# SoC.net
KiCad netlist of a schematic drawn in Altium Designer
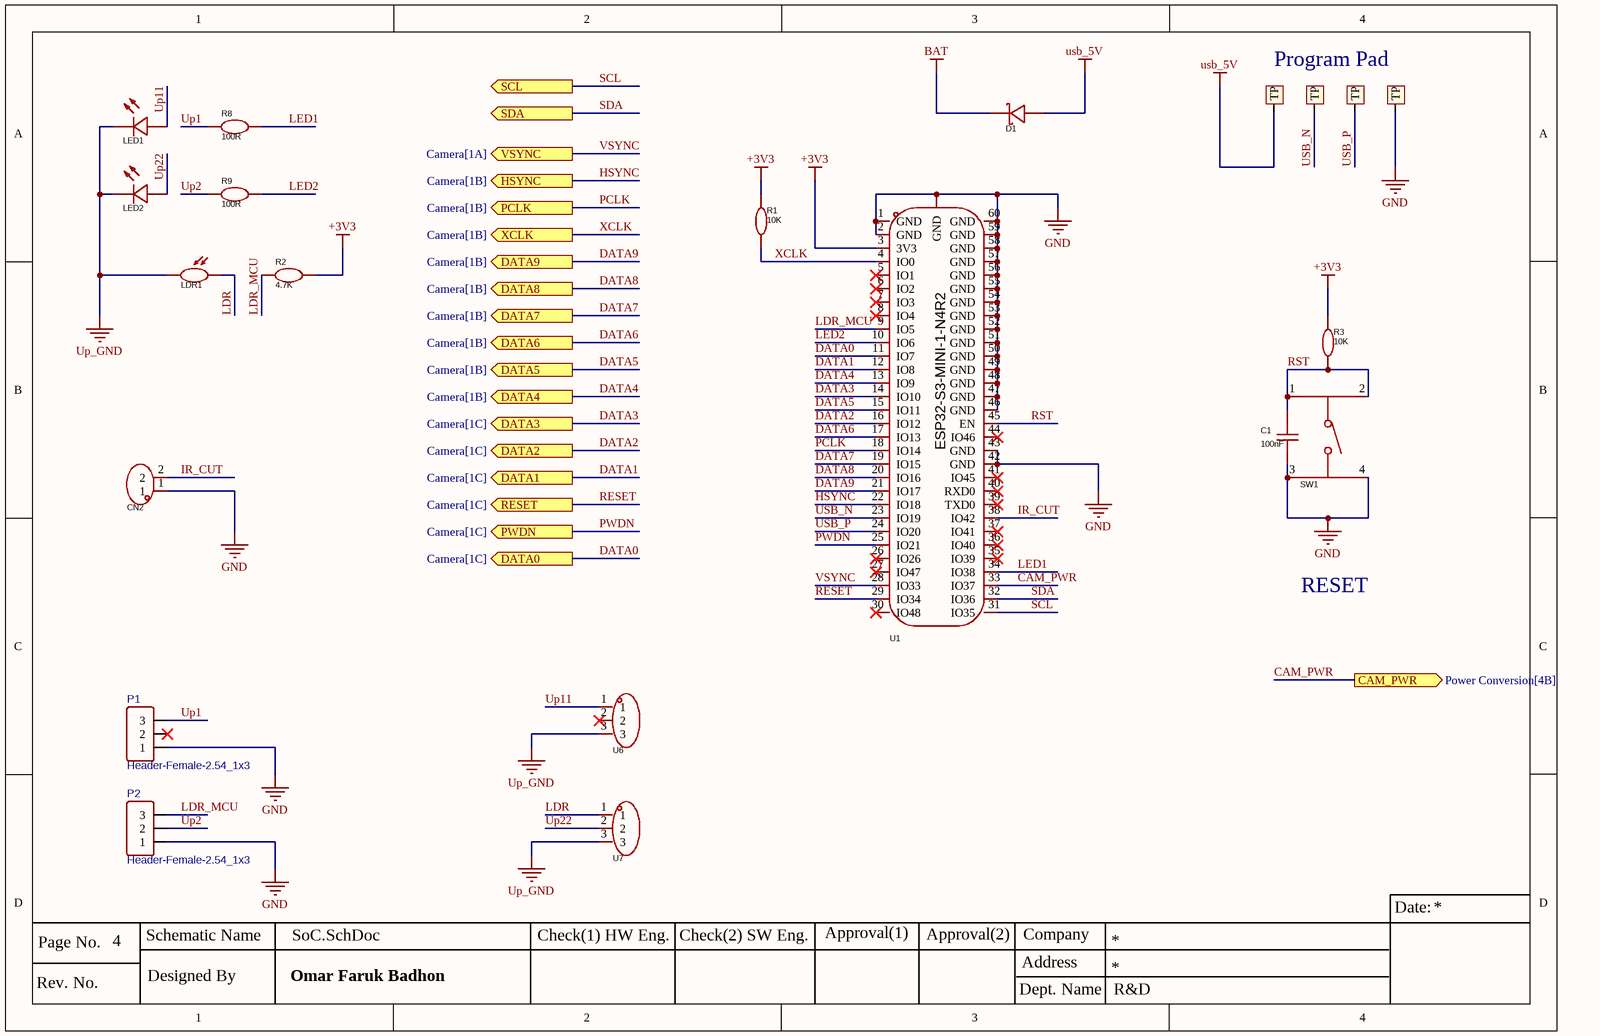
[diagram p0: SoC.SchDoc]

(export (version "E")
  (design (tool "Eeschema 10.0.6"))
  (components
    (comp (ref "C1")
      (value "100nF")
      (footprint "100nF SMD Ceramic 201")
      (description "10V 100nF X5R ±10% 0201 Multilayer Ceramic Capacitors MLCC - SMD/SMT ROHS")
      (fields
        (field (name "MANUFACTURER") "muRata(村田)")
        (field (name "MANUFACTURER PART") "GRM033R61A104KE84D")
      )
      (libsource (lib "Esp32 CAM SCH") (part "100nF SMD Ceramic 201"))
    )
    (comp (ref "CN2")
      (value "HDGC1501WV-2P")
      (footprint "2P white Connector 1.5mm")
      (fields (field (name "MANUFACTURER") "HDGC(华德共创)"))
      (libsource (lib "Esp32 CAM SCH") (part "2P Connector 1.5mm"))
    )
    (comp (ref "D1")
      (value "MBR120VLSFT1G")
      (footprint "Schottky Diode")
      (description "20V 300mV@1A 1A SOD-123FL Schottky Diodes ROHS")
      (fields (field (name "MANUFACTURER") "onsemi(安森美)"))
      (libsource (lib "Esp32 CAM SCH") (part "Schottky Diode"))
    )
    (comp (ref "LDR1")
      (value "GT36528")
      (footprint "LDR")
      (description "SMD,2.4x3.6mm Photoresistors ROHS")
      (fields (field (name "MANUFACTURER") "JCHL(晶创和立)"))
      (libsource (lib "Esp32 CAM SCH") (part "LDR"))
    )
    (comp (ref "LED1")
      (value "XYC-IRC18C-24")
      (footprint "LED SMD")
      (fields (field (name "MANUFACTURER") "NEWOPTO(鑫永诚光电)"))
      (libsource (lib "Esp32 CAM SCH") (part "LED SMD"))
    )
    (comp (ref "LED2")
      (value "XYC-IRC18C-24")
      (footprint "LED SMD")
      (fields (field (name "MANUFACTURER") "NEWOPTO(鑫永诚光电)"))
      (libsource (lib "Esp32 CAM SCH") (part "LED SMD"))
    )
    (comp (ref "P1")
      (value "Header-Female-2.54_1x3")
      (footprint "3P FH 2.54mm")
      (fields (field (name "MANUFACTURER") "BOOMELE(博穆精密)") (field (name "MANUFACTURER PART") "2.54-1*3P母"))
      (libsource (lib "Esp32 CAM SCH") (part "Header-Female-2.54_1x3"))
    )
    (comp (ref "P2")
      (value "Header-Female-2.54_1x3")
      (footprint "3P FH 2.54mm")
      (fields (field (name "MANUFACTURER") "BOOMELE(博穆精密)") (field (name "MANUFACTURER PART") "2.54-1*3P母"))
      (libsource (lib "Esp32 CAM SCH") (part "Header-Female-2.54_1x3"))
    )
    (comp (ref "R1")
      (value "10K")
      (footprint "10K SMD Ceramic 201")
      (description "50mW Thick Film Resistors 25V ±1% ±200ppm/℃ 10kΩ 0201 Chip Resistor - Surface Mount ROHS")
      (fields (field (name "MANUFACTURER") "YAGEO(国巨)") (field (name "MANUFACTURER PART") "AF0201FR-0710KL"))
      (libsource (lib "Esp32 CAM SCH") (part "10K SMD Ceramic 201"))
    )
    (comp (ref "R2")
      (value "4.7K")
      (footprint "4k7 SMD 201")
      (description "50mW Thick Film Resistors 25V ±1% ±200ppm/℃ 4.7kΩ 0201 Chip Resistor - Surface Mount ROHS")
      (fields (field (name "MANUFACTURER") "YAGEO(国巨)") (field (name "MANUFACTURER PART") "AF0201FR-074K7L"))
      (libsource (lib "Esp32 CAM SCH") (part "4K7 SMD 201"))
    )
    (comp (ref "R3")
      (value "10K")
      (footprint "10K SMD Ceramic 201")
      (description "50mW Thick Film Resistors 25V ±1% ±200ppm/℃ 10kΩ 0201 Chip Resistor - Surface Mount ROHS")
      (fields (field (name "MANUFACTURER") "YAGEO(国巨)") (field (name "MANUFACTURER PART") "AF0201FR-0710KL"))
      (libsource (lib "Esp32 CAM SCH") (part "10K SMD Ceramic 201"))
    )
    (comp (ref "R8")
      (value "100R")
      (footprint "100R 402")
      (description "100mW Thick Film Resistors ±100ppm/℃ ±1% 100Ω 0402 Chip Resistor - Surface Mount ROHS")
      (fields (field (name "MANUFACTURER") "PANASONIC(松下)") (field (name "MANUFACTURER PART") "ERJ2RKF1000X"))
      (libsource (lib "Esp32 CAM SCH") (part "100R 402"))
    )
    (comp (ref "R9")
      (value "100R")
      (footprint "100R 402")
      (description "100mW Thick Film Resistors ±100ppm/℃ ±1% 100Ω 0402 Chip Resistor - Surface Mount ROHS")
      (fields (field (name "MANUFACTURER") "PANASONIC(松下)") (field (name "MANUFACTURER PART") "ERJ2RKF1000X"))
      (libsource (lib "Esp32 CAM SCH") (part "100R 402"))
    )
    (comp (ref "SW1")
      (value "TS-1102-5516")
      (footprint "Push Button 4P")
      (fields (field (name "MANUFACTURER") "SOFNG(硕方)"))
      (libsource (lib "Esp32 CAM SCH") (part "Push Button 4P"))
    )
    (comp (ref "TP1")
      (value "TEST POINT")
      (footprint "TESTPOINT")
      (libsource (lib "Esp32 CAM SCH") (part "TEST POINT"))
    )
    (comp (ref "TP2")
      (value "TEST POINT")
      (footprint "TESTPOINT")
      (libsource (lib "Esp32 CAM SCH") (part "TEST POINT"))
    )
    (comp (ref "TP3")
      (value "TEST POINT")
      (footprint "TESTPOINT")
      (libsource (lib "Esp32 CAM SCH") (part "TEST POINT"))
    )
    (comp (ref "TP4")
      (value "TEST POINT")
      (footprint "TESTPOINT")
      (libsource (lib "Esp32 CAM SCH") (part "TEST POINT"))
    )
    (comp (ref "U1")
      (value "ESP32-S3-MINI-1-N4R2")
      (footprint "ESP32-S3-MINI-1-N8")
      (fields (field (name "MANUFACTURER") "ESPRESSIF(乐鑫)"))
      (libsource (lib "Esp32 CAM SCH") (part "ESP32-S3-MINI-1-N4R2"))
    )
    (comp (ref "U6")
      (value "HB-PH3-25413PB2GOP")
      (footprint "3P MH 2.54mm")
      (fields (field (name "MANUFACTURER") "HANBO(汉博)"))
      (libsource (lib "Esp32 CAM SCH") (part "3P MH 2.54mm"))
    )
    (comp (ref "U7")
      (value "HB-PH3-25413PB2GOP")
      (footprint "3P MH 2.54mm")
      (fields (field (name "MANUFACTURER") "HANBO(汉博)"))
      (libsource (lib "Esp32 CAM SCH") (part "3P MH 2.54mm"))
    )
  )
  (nets
    (net (code "1") (name "+3V3") (class "Default")
      (node (ref "R1") (pin "2") (pinfunction "2_2") (pintype "passive"))
      (node (ref "R2") (pin "1") (pinfunction "1_1") (pintype "passive"))
      (node (ref "R3") (pin "2") (pinfunction "2_2") (pintype "passive"))
      (node (ref "U1") (pin "3") (pinfunction "3V3_3") (pintype "passive"))
    )
    (net (code "2") (name "/CAM_PWR") (class "Default")
      (node (ref "U1") (pin "33") (pinfunction "IO37_33") (pintype "passive"))
    )
    (net (code "3") (name "/DATA0") (class "Default")
      (node (ref "U1") (pin "11") (pinfunction "IO7_11") (pintype "passive"))
    )
    (net (code "4") (name "/DATA1") (class "Default")
      (node (ref "U1") (pin "12") (pinfunction "IO8_12") (pintype "passive"))
    )
    (net (code "5") (name "/DATA2") (class "Default")
      (node (ref "U1") (pin "16") (pinfunction "IO12_16") (pintype "passive"))
    )
    (net (code "6") (name "/DATA3") (class "Default")
      (node (ref "U1") (pin "14") (pinfunction "IO10_14") (pintype "passive"))
    )
    (net (code "7") (name "/DATA4") (class "Default")
      (node (ref "U1") (pin "13") (pinfunction "IO9_13") (pintype "passive"))
    )
    (net (code "8") (name "/DATA5") (class "Default")
      (node (ref "U1") (pin "15") (pinfunction "IO11_15") (pintype "passive"))
    )
    (net (code "9") (name "/DATA6") (class "Default")
      (node (ref "U1") (pin "17") (pinfunction "IO13_17") (pintype "passive"))
    )
    (net (code "10") (name "/DATA7") (class "Default")
      (node (ref "U1") (pin "19") (pinfunction "IO15_19") (pintype "passive"))
    )
    (net (code "11") (name "/DATA8") (class "Default")
      (node (ref "U1") (pin "20") (pinfunction "IO16_20") (pintype "passive"))
    )
    (net (code "12") (name "/DATA9") (class "Default")
      (node (ref "U1") (pin "21") (pinfunction "IO17_21") (pintype "passive"))
    )
    (net (code "13") (name "/HSYNC") (class "Default")
      (node (ref "U1") (pin "22") (pinfunction "IO18_22") (pintype "passive"))
    )
    (net (code "14") (name "/IR_CUT") (class "Default")
      (node (ref "CN2") (pin "2") (pinfunction "2_2") (pintype "passive"))
      (node (ref "U1") (pin "38") (pinfunction "IO42_38") (pintype "passive"))
    )
    (net (code "15") (name "/LDR") (class "Default")
      (node (ref "LDR1") (pin "2") (pinfunction "2_2") (pintype "passive"))
      (node (ref "U7") (pin "1") (pinfunction "1_1") (pintype "passive"))
    )
    (net (code "16") (name "/LDR_MCU") (class "Default")
      (node (ref "P2") (pin "3") (pinfunction "3_3") (pintype "passive"))
      (node (ref "R2") (pin "2") (pinfunction "2_2") (pintype "passive"))
      (node (ref "U1") (pin "9") (pinfunction "IO5_9") (pintype "passive"))
    )
    (net (code "17") (name "/LED1") (class "Default")
      (node (ref "R8") (pin "2") (pinfunction "2_2") (pintype "passive"))
      (node (ref "U1") (pin "34") (pinfunction "IO38_34") (pintype "passive"))
    )
    (net (code "18") (name "/LED2") (class "Default")
      (node (ref "R9") (pin "2") (pinfunction "2_2") (pintype "passive"))
      (node (ref "U1") (pin "10") (pinfunction "IO6_10") (pintype "passive"))
    )
    (net (code "19") (name "/PCLK") (class "Default")
      (node (ref "U1") (pin "18") (pinfunction "IO14_18") (pintype "passive"))
    )
    (net (code "20") (name "/PWDN") (class "Default")
      (node (ref "U1") (pin "25") (pinfunction "IO21_25") (pintype "passive"))
    )
    (net (code "21") (name "/RESET") (class "Default")
      (node (ref "U1") (pin "29") (pinfunction "IO34_29") (pintype "passive"))
    )
    (net (code "22") (name "/RST") (class "Default")
      (node (ref "C1") (pin "2") (pinfunction "2_2") (pintype "passive"))
      (node (ref "R3") (pin "1") (pinfunction "1_1") (pintype "passive"))
      (node (ref "SW1") (pin "1") (pinfunction "1_1") (pintype "passive"))
      (node (ref "SW1") (pin "2") (pinfunction "2_2") (pintype "passive"))
      (node (ref "U1") (pin "45") (pinfunction "EN_45") (pintype "passive"))
    )
    (net (code "23") (name "/SCL") (class "Default")
      (node (ref "U1") (pin "31") (pinfunction "IO35_31") (pintype "passive"))
    )
    (net (code "24") (name "/SDA") (class "Default")
      (node (ref "U1") (pin "32") (pinfunction "IO36_32") (pintype "passive"))
    )
    (net (code "25") (name "/USB_N") (class "Default")
      (node (ref "TP2") (pin "1") (pinfunction "TP_1") (pintype "passive"))
      (node (ref "U1") (pin "23") (pinfunction "IO19_23") (pintype "passive"))
    )
    (net (code "26") (name "/USB_P") (class "Default")
      (node (ref "TP3") (pin "1") (pinfunction "TP_1") (pintype "passive"))
      (node (ref "U1") (pin "24") (pinfunction "IO20_24") (pintype "passive"))
    )
    (net (code "27") (name "/Up1") (class "Default")
      (node (ref "P1") (pin "3") (pinfunction "3_3") (pintype "passive"))
      (node (ref "R8") (pin "1") (pinfunction "1_1") (pintype "passive"))
    )
    (net (code "28") (name "/Up2") (class "Default")
      (node (ref "P2") (pin "2") (pinfunction "2_2") (pintype "passive"))
      (node (ref "R9") (pin "1") (pinfunction "1_1") (pintype "passive"))
    )
    (net (code "29") (name "/Up11") (class "Default")
      (node (ref "LED1") (pin "2") (pinfunction "A_2") (pintype "passive"))
      (node (ref "U6") (pin "1") (pinfunction "1_1") (pintype "passive"))
    )
    (net (code "30") (name "/Up22") (class "Default")
      (node (ref "LED2") (pin "2") (pinfunction "A_2") (pintype "passive"))
      (node (ref "U7") (pin "2") (pinfunction "2_2") (pintype "passive"))
    )
    (net (code "31") (name "/VSYNC") (class "Default")
      (node (ref "U1") (pin "28") (pinfunction "IO33_28") (pintype "passive"))
    )
    (net (code "32") (name "/XCLK") (class "Default")
      (node (ref "R1") (pin "1") (pinfunction "1_1") (pintype "passive"))
      (node (ref "U1") (pin "4") (pinfunction "IO0_4") (pintype "passive"))
    )
    (net (code "33") (name "BAT") (class "Default")
      (node (ref "D1") (pin "1") (pinfunction "K_1") (pintype "passive"))
    )
    (net (code "34") (name "GND") (class "Default")
      (node (ref "C1") (pin "1") (pinfunction "1_1") (pintype "passive"))
      (node (ref "CN2") (pin "1") (pinfunction "1_1") (pintype "passive"))
      (node (ref "P1") (pin "1") (pinfunction "1_1") (pintype "passive"))
      (node (ref "P2") (pin "1") (pinfunction "1_1") (pintype "passive"))
      (node (ref "SW1") (pin "3") (pinfunction "3_3") (pintype "passive"))
      (node (ref "SW1") (pin "4") (pinfunction "4_4") (pintype "passive"))
      (node (ref "TP4") (pin "1") (pinfunction "TP_1") (pintype "passive"))
      (node (ref "U1") (pin "1") (pinfunction "GND_1") (pintype "passive"))
      (node (ref "U1") (pin "2") (pinfunction "GND_2") (pintype "passive"))
      (node (ref "U1") (pin "42") (pinfunction "GND_42") (pintype "passive"))
      (node (ref "U1") (pin "43") (pinfunction "GND_43") (pintype "passive"))
      (node (ref "U1") (pin "46") (pinfunction "GND_46") (pintype "passive"))
      (node (ref "U1") (pin "47") (pinfunction "GND_47") (pintype "passive"))
      (node (ref "U1") (pin "48") (pinfunction "GND_48") (pintype "passive"))
      (node (ref "U1") (pin "49") (pinfunction "GND_49") (pintype "passive"))
      (node (ref "U1") (pin "50") (pinfunction "GND_50") (pintype "passive"))
      (node (ref "U1") (pin "51") (pinfunction "GND_51") (pintype "passive"))
      (node (ref "U1") (pin "52") (pinfunction "GND_52") (pintype "passive"))
      (node (ref "U1") (pin "53") (pinfunction "GND_53") (pintype "passive"))
      (node (ref "U1") (pin "54") (pinfunction "GND_54") (pintype "passive"))
      (node (ref "U1") (pin "55") (pinfunction "GND_55") (pintype "passive"))
      (node (ref "U1") (pin "56") (pinfunction "GND_56") (pintype "passive"))
      (node (ref "U1") (pin "57") (pinfunction "GND_57") (pintype "passive"))
      (node (ref "U1") (pin "58") (pinfunction "GND_58") (pintype "passive"))
      (node (ref "U1") (pin "59") (pinfunction "GND_59") (pintype "passive"))
      (node (ref "U1") (pin "60") (pinfunction "GND_60") (pintype "passive"))
      (node (ref "U1") (pin "GND") (pinfunction "GND_GND") (pintype "passive"))
    )
    (net (code "35") (name "Up_GND") (class "Default")
      (node (ref "LDR1") (pin "1") (pinfunction "1_1") (pintype "passive"))
      (node (ref "LED1") (pin "1") (pinfunction "C_1") (pintype "passive"))
      (node (ref "LED2") (pin "1") (pinfunction "C_1") (pintype "passive"))
      (node (ref "U6") (pin "3") (pinfunction "3_3") (pintype "passive"))
      (node (ref "U7") (pin "3") (pinfunction "3_3") (pintype "passive"))
    )
    (net (code "36") (name "unconnected-(P1-Pad2)") (class "Default")
      (node (ref "P1") (pin "2") (pinfunction "2_2") (pintype "passive+no_connect"))
    )
    (net (code "37") (name "unconnected-(U1-IO1-Pad5)") (class "Default")
      (node (ref "U1") (pin "5") (pinfunction "IO1_5") (pintype "passive+no_connect"))
    )
    (net (code "38") (name "unconnected-(U1-IO2-Pad6)") (class "Default")
      (node (ref "U1") (pin "6") (pinfunction "IO2_6") (pintype "passive+no_connect"))
    )
    (net (code "39") (name "unconnected-(U1-IO3-Pad7)") (class "Default")
      (node (ref "U1") (pin "7") (pinfunction "IO3_7") (pintype "passive+no_connect"))
    )
    (net (code "40") (name "unconnected-(U1-IO4-Pad8)") (class "Default")
      (node (ref "U1") (pin "8") (pinfunction "IO4_8") (pintype "passive+no_connect"))
    )
    (net (code "41") (name "unconnected-(U1-IO26-Pad26)") (class "Default")
      (node (ref "U1") (pin "26") (pinfunction "IO26_26") (pintype "passive+no_connect"))
    )
    (net (code "42") (name "unconnected-(U1-IO39-Pad35)") (class "Default")
      (node (ref "U1") (pin "35") (pinfunction "IO39_35") (pintype "passive+no_connect"))
    )
    (net (code "43") (name "unconnected-(U1-IO40-Pad36)") (class "Default")
      (node (ref "U1") (pin "36") (pinfunction "IO40_36") (pintype "passive+no_connect"))
    )
    (net (code "44") (name "unconnected-(U1-IO41-Pad37)") (class "Default")
      (node (ref "U1") (pin "37") (pinfunction "IO41_37") (pintype "passive+no_connect"))
    )
    (net (code "45") (name "unconnected-(U1-IO45-Pad41)") (class "Default")
      (node (ref "U1") (pin "41") (pinfunction "IO45_41") (pintype "passive+no_connect"))
    )
    (net (code "46") (name "unconnected-(U1-IO46-Pad44)") (class "Default")
      (node (ref "U1") (pin "44") (pinfunction "IO46_44") (pintype "passive+no_connect"))
    )
    (net (code "47") (name "unconnected-(U1-IO47-Pad27)") (class "Default")
      (node (ref "U1") (pin "27") (pinfunction "IO47_27") (pintype "passive+no_connect"))
    )
    (net (code "48") (name "unconnected-(U1-IO48-Pad30)") (class "Default")
      (node (ref "U1") (pin "30") (pinfunction "IO48_30") (pintype "passive+no_connect"))
    )
    (net (code "49") (name "unconnected-(U1-RXD0-Pad40)") (class "Default")
      (node (ref "U1") (pin "40") (pinfunction "RXD0_40") (pintype "passive+no_connect"))
    )
    (net (code "50") (name "unconnected-(U1-TXD0-Pad39)") (class "Default")
      (node (ref "U1") (pin "39") (pinfunction "TXD0_39") (pintype "passive+no_connect"))
    )
    (net (code "51") (name "unconnected-(U6-Pad2)") (class "Default")
      (node (ref "U6") (pin "2") (pinfunction "2_2") (pintype "passive+no_connect"))
    )
    (net (code "52") (name "usb_5V") (class "Default")
      (node (ref "D1") (pin "2") (pinfunction "A_2") (pintype "passive"))
      (node (ref "TP1") (pin "1") (pinfunction "TP_1") (pintype "passive"))
    )
  )
)
